# Power_Lin_only.net
KiCad netlist of a schematic drawn in Altium Designer
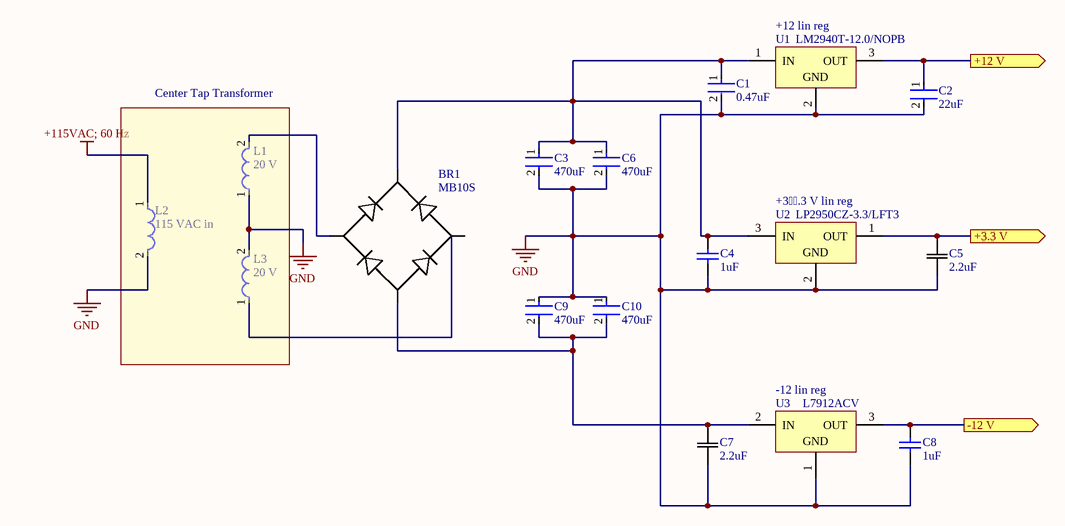
[diagram p0: Power_Lin_only.SchDoc]

(export (version "E")
  (design (tool "Eeschema 10.0.6"))
  (components
    (comp (ref "BR1")
      (value "MB10S")
      (footprint "HDS_DIO")
      (description "No Description Available")
      (fields
        (field (name "MANUFACTURER_PART_NUMBER") "HDS10M-13")
        (field (name "COPYRIGHT") "Copyright (C) 2021 Ultra Librarian. All rights reserved.")
      )
      (libsource (lib "HDS10M-13") (part "HDS10M-13"))
    )
    (comp (ref "C1")
      (value "0.47uF")
      (footprint "FP-C0603C-CF-MFG")
      (description "Cap Ceramic 0.33uF 16V X7R 10% SMD 0603 125°C Punched Paper T/R")
      (fields (field (name "TOLERANCE") "0.1") (field (name "MANUFACTURER PART NUMBER") "C0603C334K4RACAUTO"))
      (libsource (lib "Altium Content Vault") (part "b4654b650e69147ec39a6b967a45e02"))
    )
    (comp (ref "C2")
      (value "22uF")
      (footprint "FP-C0603C-CF-MFG")
      (description "CAP CER 0.1UF 50V X7R 0603")
      (fields (field (name "TOLERANCE") "0.1") (field (name "MANUFACTURER") "KEMET"))
      (libsource (lib "Altium Content Vault") (part "b4654b650e69147ec39a6b967a45e02"))
    )
    (comp (ref "C3")
      (value "470uF")
      (footprint "FP-C0603C-CF-MFG")
      (description "Cap Ceramic 0.33uF 16V X7R 10% SMD 0603 125°C Punched Paper T/R")
      (fields (field (name "TOLERANCE") "0.1") (field (name "MANUFACTURER PART NUMBER") "C0603C334K4RACAUTO"))
      (libsource (lib "Altium Content Vault") (part "b4654b650e69147ec39a6b967a45e02"))
    )
    (comp (ref "C4")
      (value "1uF")
      (footprint "CAPC3216X110X50LL20T25")
      (description "Chip Capacitor, 1 uF, +/- 10%, 50 V, -55 to 125 degC, 1206 (3216 Metric), RoHS, Tape and Reel")
      (fields (field (name "MANUFACTURER") "Kemet") (field (name "TOLERANCE") "10%"))
      (libsource (lib "Altium Content Vault") (part "CAP-NP-2"))
    )
    (comp (ref "C5")
      (value "2.2uF")
      (footprint "CAPC340180_180N_KEM")
      (description "2.2uF Ceramic cap")
      (fields
        (field (name "MANUFACTURER_PART_NUMBER") "C1206C225K5RACTU")
        (field (name "COPYRIGHT") "Copyright (C) 2021 Ultra Librarian. All rights reserved.")
      )
      (libsource (lib "C1206C225K5RACTU") (part "C1206C225K5RACTU"))
    )
    (comp (ref "C6")
      (value "470uF")
      (footprint "FP-C0603C-CF-MFG")
      (description "Cap Ceramic 0.33uF 16V X7R 10% SMD 0603 125°C Punched Paper T/R")
      (fields (field (name "TOLERANCE") "0.1") (field (name "MANUFACTURER PART NUMBER") "C0603C334K4RACAUTO"))
      (libsource (lib "Altium Content Vault") (part "b4654b650e69147ec39a6b967a45e02"))
    )
    (comp (ref "C7")
      (value "2.2uF")
      (footprint "CAPC340180_180N_KEM")
      (description "2.2uF Ceramic cap")
      (fields
        (field (name "MANUFACTURER_PART_NUMBER") "C1206C225K5RACTU")
        (field (name "COPYRIGHT") "Copyright (C) 2021 Ultra Librarian. All rights reserved.")
      )
      (libsource (lib "C1206C225K5RACTU") (part "C1206C225K5RACTU"))
    )
    (comp (ref "C8")
      (value "1uF")
      (footprint "CAPC3216X110X50LL20T25")
      (description "Chip Capacitor, 1 uF, +/- 10%, 50 V, -55 to 125 degC, 1206 (3216 Metric), RoHS, Tape and Reel")
      (fields (field (name "MANUFACTURER") "Kemet") (field (name "TOLERANCE") "10%"))
      (libsource (lib "Altium Content Vault") (part "CAP-NP-2"))
    )
    (comp (ref "C9")
      (value "470uF")
      (footprint "FP-C0603C-CF-MFG")
      (description "Cap Ceramic 0.33uF 16V X7R 10% SMD 0603 125°C Punched Paper T/R")
      (fields (field (name "TOLERANCE") "0.1") (field (name "MANUFACTURER PART NUMBER") "C0603C334K4RACAUTO"))
      (libsource (lib "Altium Content Vault") (part "b4654b650e69147ec39a6b967a45e02"))
    )
    (comp (ref "C10")
      (value "470uF")
      (footprint "FP-C0603C-CF-MFG")
      (description "Cap Ceramic 0.33uF 16V X7R 10% SMD 0603 125°C Punched Paper T/R")
      (fields (field (name "TOLERANCE") "0.1") (field (name "MANUFACTURER PART NUMBER") "C0603C334K4RACAUTO"))
      (libsource (lib "Altium Content Vault") (part "b4654b650e69147ec39a6b967a45e02"))
    )
    (comp (ref "L1")
      (value "20 V")
      (footprint "FP-LQH55DN_03-MFG")
      (description "Wire Wound Ferrite Inductor for Power Lines 220μH ±20% 3.36Ω  0.32A 2220")
      (fields (field (name "TOLERANCE") "20%"))
      (libsource (lib "Altium Content Vault") (part "725321dda6339637d4d059423bc1c3c"))
    )
    (comp (ref "L2")
      (value "115 VAC in")
      (footprint "FP-LQH55DN_03-MFG")
      (description "Wire Wound Ferrite Inductor for Power Lines 220μH ±20% 3.36Ω  0.32A 2220")
      (fields (field (name "TOLERANCE") "20%"))
      (libsource (lib "Altium Content Vault") (part "725321dda6339637d4d059423bc1c3c"))
    )
    (comp (ref "L3")
      (value "20 V")
      (footprint "FP-LQH55DN_03-MFG")
      (description "Wire Wound Ferrite Inductor for Power Lines 220μH ±20% 3.36Ω  0.32A 2220")
      (fields (field (name "TOLERANCE") "20%"))
      (libsource (lib "Altium Content Vault") (part "725321dda6339637d4d059423bc1c3c"))
    )
    (comp (ref "U1")
      (value "LM2940T-12.0/NOPB")
      (footprint "NDE0003A")
      (description "1A Low Dropout Regulator, 3-pin TO-220, Pb-Free")
      (fields (field (name "MANUFACTURER") "Texas Instruments"))
      (libsource (lib "Altium Content Vault") (part "PM-REG-LM2940-SIL3"))
    )
    (comp (ref "U2")
      (value "LP2950CZ-3.3/LFT3")
      (footprint "LP0003A")
      (description "Series of Adjustable Micropower Voltage Regulators, 3-pin TO-92, Pb-Free")
      (fields (field (name "MANUFACTURER") "Texas Instruments"))
      (libsource (lib "Altium Content Vault") (part "PM-REG-LM78L05-SIL3"))
    )
    (comp (ref "U3")
      (value "L7912ACV")
      (footprint "TO220")
      (description "2% Negative Voltage Regulator, -12V, 3-Pin TO-220")
      (libsource (lib "Altium Content Vault") (part "PM-REG-7905-SIL3"))
    )
  )
  (nets
    (net (code "1") (name "+115VAC; 60 Hz") (class "Default")
      (node (ref "L2") (pin "1") (pinfunction "1_1") (pintype "passive"))
    )
    (net (code "2") (name "/+3.3 V") (class "Default")
      (node (ref "C5") (pin "2") (pinfunction "2_2") (pintype "passive"))
      (node (ref "U2") (pin "1") (pinfunction "OUT_1") (pintype "power_in"))
    )
    (net (code "3") (name "/+12 V") (class "Default")
      (node (ref "C2") (pin "1") (pinfunction "1_1") (pintype "passive"))
      (node (ref "U1") (pin "3") (pinfunction "OUT_3") (pintype "power_in"))
    )
    (net (code "4") (name "/-12 V") (class "Default")
      (node (ref "C8") (pin "2") (pinfunction "2_2") (pintype "passive"))
      (node (ref "U3") (pin "3") (pinfunction "OUT_3") (pintype "power_in"))
    )
    (net (code "5") (name "GND") (class "Default")
      (node (ref "C1") (pin "2") (pinfunction "2_2") (pintype "passive"))
      (node (ref "C10") (pin "1") (pinfunction "1_1") (pintype "passive"))
      (node (ref "C2") (pin "2") (pinfunction "2_2") (pintype "passive"))
      (node (ref "C3") (pin "2") (pinfunction "2_2") (pintype "passive"))
      (node (ref "C4") (pin "1") (pinfunction "1_1") (pintype "passive"))
      (node (ref "C5") (pin "1") (pinfunction "1_1") (pintype "passive"))
      (node (ref "C6") (pin "2") (pinfunction "2_2") (pintype "passive"))
      (node (ref "C7") (pin "1") (pinfunction "1_1") (pintype "passive"))
      (node (ref "C8") (pin "1") (pinfunction "1_1") (pintype "passive"))
      (node (ref "C9") (pin "1") (pinfunction "1_1") (pintype "passive"))
      (node (ref "L1") (pin "1") (pinfunction "1_1") (pintype "passive"))
      (node (ref "L2") (pin "2") (pinfunction "2_2") (pintype "passive"))
      (node (ref "L3") (pin "2") (pinfunction "2_2") (pintype "passive"))
      (node (ref "U1") (pin "2") (pinfunction "GND_2") (pintype "power_in"))
      (node (ref "U2") (pin "2") (pinfunction "GND_2") (pintype "power_in"))
      (node (ref "U3") (pin "1") (pinfunction "GND_1") (pintype "power_in"))
    )
    (net (code "6") (name "Net-(BR1-Pad2)") (class "Default")
      (node (ref "BR1") (pin "2") (pinfunction "2_2") (pintype "passive"))
      (node (ref "L1") (pin "2") (pinfunction "2_2") (pintype "passive"))
    )
    (net (code "7") (name "Net-(U1-IN)") (class "Default")
      (node (ref "BR1") (pin "1") (pinfunction "1_1") (pintype "passive"))
      (node (ref "C1") (pin "1") (pinfunction "1_1") (pintype "passive"))
      (node (ref "C3") (pin "1") (pinfunction "1_1") (pintype "passive"))
      (node (ref "C4") (pin "2") (pinfunction "2_2") (pintype "passive"))
      (node (ref "C6") (pin "1") (pinfunction "1_1") (pintype "passive"))
      (node (ref "U1") (pin "1") (pinfunction "IN_1") (pintype "power_in"))
      (node (ref "U2") (pin "3") (pinfunction "IN_3") (pintype "power_in"))
    )
    (net (code "8") (name "Net-(U3-IN)") (class "Default")
      (node (ref "BR1") (pin "3") (pinfunction "3_3") (pintype "passive"))
      (node (ref "C10") (pin "2") (pinfunction "2_2") (pintype "passive"))
      (node (ref "C7") (pin "2") (pinfunction "2_2") (pintype "passive"))
      (node (ref "C9") (pin "2") (pinfunction "2_2") (pintype "passive"))
      (node (ref "U3") (pin "2") (pinfunction "IN_2") (pintype "power_in"))
    )
    (net (code "9") (name "unconnected-(BR1-Pad4)") (class "Default")
      (node (ref "BR1") (pin "4") (pinfunction "4_4") (pintype "passive"))
    )
    (net (code "10") (name "unconnected-(L3-Pad1)") (class "Default")
      (node (ref "L3") (pin "1") (pinfunction "1_1") (pintype "passive"))
    )
  )
)
